# Power.net
KiCad netlist of a schematic drawn in Altium Designer
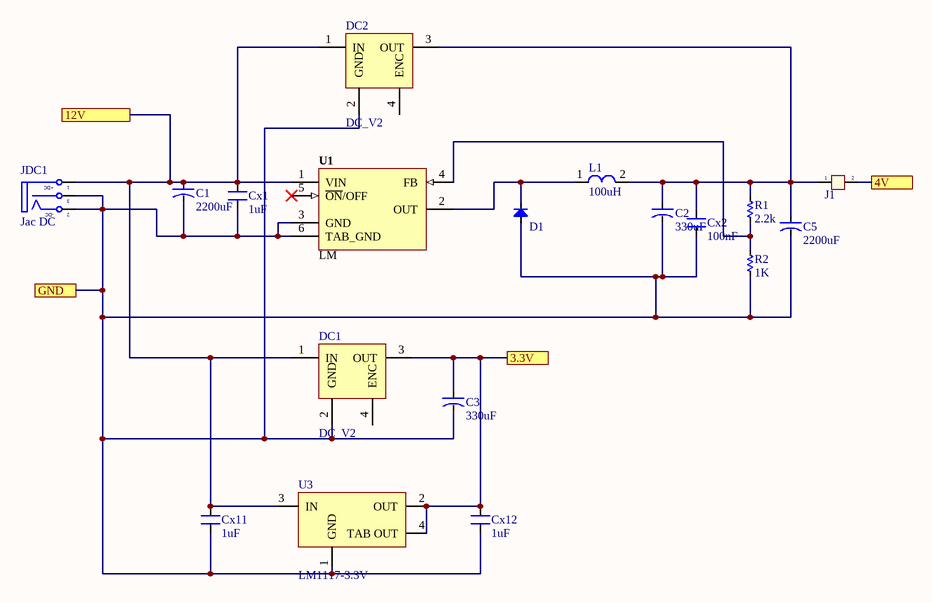
[diagram p0: Power.SchDoc]

(export (version "E")
  (design (tool "Eeschema 10.0.6"))
  (components
    (comp (ref "C1")
      (value "2200uF")
      (footprint "CA-ALU-5")
      (description "Capacitor (Semiconductor SIM Model)")
      (fields (field (name "PUBLISHER") "Altium Limited"))
      (libsource (lib "LIBRARY") (part "CN-ALU-DIP"))
    )
    (comp (ref "C2")
      (value "330uF")
      (footprint "CA-ALU-5")
      (description "Capacitor (Semiconductor SIM Model)")
      (fields (field (name "PUBLISHER") "Altium Limited"))
      (libsource (lib "LIBRARY") (part "CN-ALU-DIP"))
    )
    (comp (ref "C3")
      (value "330uF")
      (footprint "CA-ALU-5")
      (description "Capacitor (Semiconductor SIM Model)")
      (fields (field (name "PUBLISHER") "Altium Limited"))
      (libsource (lib "LIBRARY") (part "CN-ALU-DIP"))
    )
    (comp (ref "C5")
      (value "2200uF")
      (footprint "CA-ALU-5")
      (description "Capacitor (Semiconductor SIM Model)")
      (fields (field (name "PUBLISHER") "Altium Limited"))
      (libsource (lib "LIBRARY") (part "CN-ALU-DIP"))
    )
    (comp (ref "Cx1") (value "1uF") (footprint "CN-SMD-0805") (libsource (lib "LIBRARY") (part "CN")))
    (comp (ref "Cx2") (value "100nF") (footprint "CN-SMD-0805") (libsource (lib "LIBRARY") (part "CN")))
    (comp (ref "Cx11") (value "1uF") (footprint "CN-SMD-0805") (libsource (lib "LIBRARY") (part "CN")))
    (comp (ref "Cx12") (value "1uF") (footprint "CN-SMD-0805") (libsource (lib "LIBRARY") (part "CN")))
    (comp (ref "D1")
      (value "MBR340")
      (footprint "DIO-5AN")
      (description "Default Diode")
      (fields (field (name "PUBLISHER") "Altium Limited"))
      (libsource (lib "BanLinhKien") (part "Diode"))
    )
    (comp (ref "DC1") (value "DC_V2") (footprint "DC_V2") (libsource (lib "nhan") (part "DC_Module_V2")))
    (comp (ref "DC2") (value "DC_V2") (footprint "DC_V2") (libsource (lib "nhan") (part "DC_Module_V2")))
    (comp (ref "J1") (value "Jumper 2") (footprint "JP2") (libsource (lib "syhaunguyen") (part "JP 2")))
    (comp (ref "JDC1")
      (value "Jac DC")
      (footprint "DC0")
      (description "Jac DC input")
      (libsource (lib "LIBRARY") (part "DCIN"))
    )
    (comp (ref "L1")
      (value "100uH")
      (footprint "L-SMD-M-12x10")
      (fields
        (field (name "PARTNO") "78477010")
        (field (name "MANUFACTURER") "Wurth Elektronik")
        (field (name "CREATED BY") "Baojun Chen")
      )
      (libsource (lib "LIBRARY") (part "L-SMD-1"))
    )
    (comp (ref "R1")
      (value "2.2k")
      (footprint "RES-SMD-0805")
      (description "Resistor")
      (fields
        (field (name "MANUFACTURER") "Generic Components")
        (field (name "PUBLISHER") "Altium Hobart Technology Centre")
      )
      (libsource (lib "LIBRARY") (part "Res-SMD"))
    )
    (comp (ref "R2")
      (value "1K")
      (footprint "RES-SMD-0805")
      (description "Resistor")
      (fields
        (field (name "MANUFACTURER") "Generic Components")
        (field (name "PUBLISHER") "Altium Hobart Technology Centre")
      )
      (libsource (lib "LIBRARY") (part "Res-SMD"))
    )
    (comp (ref "U1") (value "LM") (footprint "TO263 - duplicate") (libsource (lib "nhan") (part "LM2596_1")))
    (comp (ref "U3")
      (value "LM1117-3.3V")
      (footprint "SOT223")
      (description "800mA Low-Dropout Linear Regulator")
      (fields (field (name "CREATOR") "Nguyen Ba Bien"))
      (libsource (lib "nhan") (part "LM1117"))
    )
  )
  (nets
    (net (code "1") (name "/3.3V") (class "Default")
      (node (ref "C3") (pin "1") (pinfunction "1_1") (pintype "passive"))
      (node (ref "Cx12") (pin "2") (pinfunction "2_2") (pintype "passive"))
      (node (ref "DC1") (pin "3") (pinfunction "OUT_3") (pintype "power_in"))
      (node (ref "U3") (pin "2") (pinfunction "OUT_2") (pintype "passive"))
      (node (ref "U3") (pin "4") (pinfunction "TAB_OUT_4") (pintype "passive"))
    )
    (net (code "2") (name "/4V") (class "Default")
      (node (ref "J1") (pin "2") (pinfunction "2_2") (pintype "passive"))
    )
    (net (code "3") (name "/12V") (class "Default")
      (node (ref "C1") (pin "1") (pinfunction "1_1") (pintype "passive"))
      (node (ref "Cx1") (pin "2") (pinfunction "2_2") (pintype "passive"))
      (node (ref "Cx11") (pin "2") (pinfunction "2_2") (pintype "passive"))
      (node (ref "DC1") (pin "1") (pinfunction "IN_1") (pintype "power_in"))
      (node (ref "DC2") (pin "1") (pinfunction "IN_1") (pintype "power_in"))
      (node (ref "JDC1") (pin "1") (pinfunction "T_1") (pintype "passive"))
      (node (ref "U1") (pin "1") (pinfunction "VIN_1") (pintype "power_in"))
      (node (ref "U3") (pin "3") (pinfunction "IN_3") (pintype "passive"))
    )
    (net (code "4") (name "/GND") (class "Default")
      (node (ref "C1") (pin "2") (pinfunction "2_2") (pintype "passive"))
      (node (ref "C2") (pin "2") (pinfunction "2_2") (pintype "passive"))
      (node (ref "C3") (pin "2") (pinfunction "2_2") (pintype "passive"))
      (node (ref "C5") (pin "2") (pinfunction "2_2") (pintype "passive"))
      (node (ref "Cx1") (pin "1") (pinfunction "1_1") (pintype "passive"))
      (node (ref "Cx11") (pin "1") (pinfunction "1_1") (pintype "passive"))
      (node (ref "Cx12") (pin "1") (pinfunction "1_1") (pintype "passive"))
      (node (ref "Cx2") (pin "1") (pinfunction "1_1") (pintype "passive"))
      (node (ref "D1") (pin "1") (pinfunction "A_1") (pintype "passive"))
      (node (ref "DC1") (pin "2") (pinfunction "GND_2") (pintype "power_in"))
      (node (ref "DC2") (pin "2") (pinfunction "GND_2") (pintype "power_in"))
      (node (ref "JDC1") (pin "2") (pinfunction "TN_2") (pintype "passive"))
      (node (ref "JDC1") (pin "3") (pinfunction "S_3") (pintype "power_in"))
      (node (ref "R2") (pin "2") (pinfunction "2_2") (pintype "passive"))
      (node (ref "U1") (pin "3") (pinfunction "GND_3") (pintype "power_in"))
      (node (ref "U1") (pin "6") (pinfunction "TAB_GND_6") (pintype "power_in"))
      (node (ref "U3") (pin "1") (pinfunction "GND_1") (pintype "passive"))
    )
    (net (code "5") (name "Net-(D1-K)") (class "Default")
      (node (ref "D1") (pin "2") (pinfunction "K_2") (pintype "passive"))
      (node (ref "L1") (pin "1") (pinfunction "1_1") (pintype "passive"))
      (node (ref "U1") (pin "2") (pinfunction "OUT_2") (pintype "power_in"))
    )
    (net (code "6") (name "Net-(DC2-OUT)") (class "Default")
      (node (ref "C2") (pin "1") (pinfunction "1_1") (pintype "passive"))
      (node (ref "C5") (pin "1") (pinfunction "1_1") (pintype "passive"))
      (node (ref "Cx2") (pin "2") (pinfunction "2_2") (pintype "passive"))
      (node (ref "DC2") (pin "3") (pinfunction "OUT_3") (pintype "power_in"))
      (node (ref "J1") (pin "1") (pinfunction "1_1") (pintype "passive"))
      (node (ref "L1") (pin "2") (pinfunction "2_2") (pintype "passive"))
      (node (ref "R1") (pin "1") (pinfunction "1_1") (pintype "passive"))
    )
    (net (code "7") (name "Net-(U1-FB)") (class "Default")
      (node (ref "R1") (pin "2") (pinfunction "2_2") (pintype "passive"))
      (node (ref "R2") (pin "1") (pinfunction "1_1") (pintype "passive"))
      (node (ref "U1") (pin "4") (pinfunction "FB_4") (pintype "input"))
    )
    (net (code "8") (name "unconnected-(DC1-ENC-Pad4)") (class "Default")
      (node (ref "DC1") (pin "4") (pinfunction "ENC_4") (pintype "power_in"))
    )
    (net (code "9") (name "unconnected-(DC2-ENC-Pad4)") (class "Default")
      (node (ref "DC2") (pin "4") (pinfunction "ENC_4") (pintype "power_in"))
    )
    (net (code "10") (name "unconnected-(U1-~{ON}{slash}OFF-Pad5)") (class "Default")
      (node (ref "U1") (pin "5") (pinfunction "~{ON}/OFF_5") (pintype "input+no_connect"))
    )
  )
)
